# Reflow-A-Tron.net
KiCad netlist of a schematic drawn in EAGLE
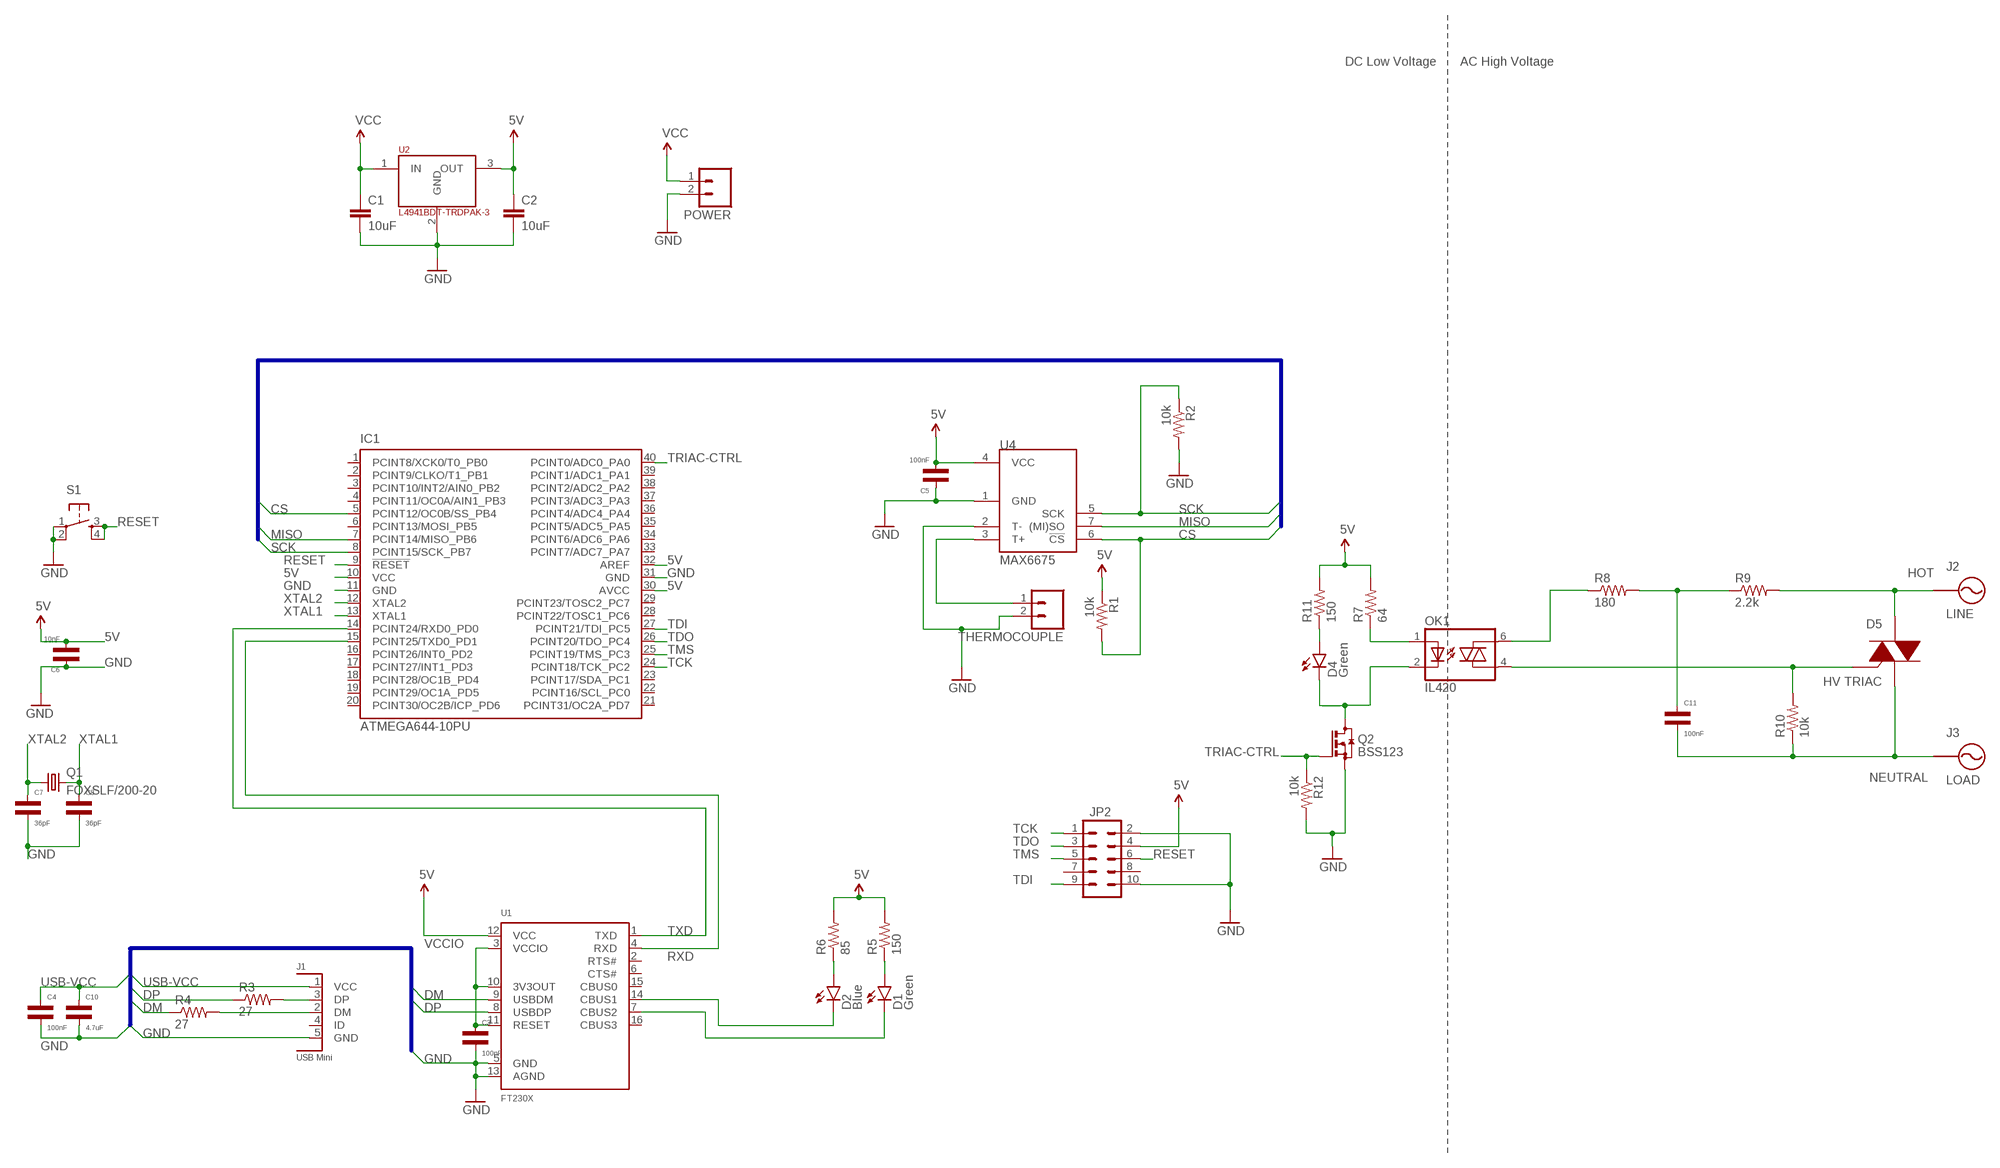
[diagram p0: schematic, sheet 1]

(export (version "E")
  (design (tool "Eeschema 10.0.6"))
  (components
    (comp (ref "C1")
      (value "10uF")
      (footprint "eagle-import:1210")
      (libsource (lib "eagle-import") (part "10UF50V20%(1210)"))
    )
    (comp (ref "C2")
      (value "10uF")
      (footprint "eagle-import:1210")
      (libsource (lib "eagle-import") (part "10UF50V20%(1210)"))
    )
    (comp (ref "C3")
      (value "100nF")
      (footprint "eagle-import:0805")
      (libsource (lib "eagle-import") (part "neilbetham_SMD-CAP-0805"))
    )
    (comp (ref "C4")
      (value "100nF")
      (footprint "eagle-import:0805")
      (libsource (lib "eagle-import") (part "neilbetham_SMD-CAP-0805"))
    )
    (comp (ref "C5")
      (value "100nF")
      (footprint "eagle-import:0805")
      (libsource (lib "eagle-import") (part "SMD-CAP-0805"))
    )
    (comp (ref "C6")
      (value "10nF")
      (footprint "eagle-import:0805")
      (libsource (lib "eagle-import") (part "SMD-CAP-0805"))
    )
    (comp (ref "C7")
      (value "36pF")
      (footprint "eagle-import:0805")
      (libsource (lib "eagle-import") (part "neilbetham_SMD-CAP-0805"))
    )
    (comp (ref "C8")
      (value "36pF")
      (footprint "eagle-import:0805")
      (libsource (lib "eagle-import") (part "neilbetham_SMD-CAP-0805"))
    )
    (comp (ref "C10")
      (value "4.7uF")
      (footprint "eagle-import:0805")
      (libsource (lib "eagle-import") (part "neilbetham_SMD-CAP-0805"))
    )
    (comp (ref "C11")
      (value "100nF")
      (footprint "eagle-import:0805")
      (libsource (lib "eagle-import") (part "neilbetham_SMD-CAP-0805"))
    )
    (comp (ref "D1")
      (value "Green")
      (footprint "eagle-import:LED-1206")
      (libsource (lib "eagle-import") (part "LED1206"))
    )
    (comp (ref "D2")
      (value "Blue")
      (footprint "eagle-import:LED-1206")
      (libsource (lib "eagle-import") (part "LED1206"))
    )
    (comp (ref "D4")
      (value "Green")
      (footprint "eagle-import:LED-1206")
      (libsource (lib "eagle-import") (part "LED1206"))
    )
    (comp (ref "D5")
      (value "HV TRIAC")
      (footprint "eagle-import:D2PAK")
      (libsource (lib "eagle-import") (part "T1250H"))
    )
    (comp (ref "IC1")
      (value "ATMEGA644-10PU")
      (footprint "eagle-import:DIL40")
      (fields (field (name "MPN") "ATMEGA644V-10PU"))
      (libsource (lib "eagle-import") (part "ATMEGA644-PU10"))
    )
    (comp (ref "J1")
      (value "USB Mini")
      (footprint "eagle-import:XM7D-0512")
      (libsource (lib "eagle-import") (part "XM7D-0512"))
    )
    (comp (ref "J2")
      (value "LINE")
      (footprint "eagle-import:8191")
      (libsource (lib "eagle-import") (part "8191"))
    )
    (comp (ref "J3")
      (value "LOAD")
      (footprint "eagle-import:8191")
      (libsource (lib "eagle-import") (part "8191"))
    )
    (comp (ref "JP2")
      (value "M05X2PTH")
      (footprint "eagle-import:AVR_ICSP")
      (libsource (lib "eagle-import") (part "M05X2PTH"))
    )
    (comp (ref "OK1")
      (value "IL420")
      (footprint "eagle-import:DIL06")
      (fields (field (name "MF") "VISHAY/TELEFUNKEN"))
      (libsource (lib "eagle-import") (part "IL420"))
    )
    (comp (ref "POWER")
      (value "M025MM")
      (footprint "eagle-import:SCREWTERMINAL-5MM-2")
      (libsource (lib "eagle-import") (part "M025MM"))
    )
    (comp (ref "Q1")
      (value "FOXSLF/200-20")
      (footprint "eagle-import:HC49_S")
      (libsource (lib "eagle-import") (part "CRYSTALHC49S"))
    )
    (comp (ref "Q2")
      (value "BSS123")
      (footprint "eagle-import:SOT23")
      (libsource (lib "eagle-import") (part "BSS123"))
    )
    (comp (ref "R1")
      (value "10k")
      (footprint "eagle-import:R0805")
      (libsource (lib "eagle-import") (part "R-US_R0805"))
    )
    (comp (ref "R2")
      (value "10k")
      (footprint "eagle-import:R0805")
      (libsource (lib "eagle-import") (part "R-US_R0805"))
    )
    (comp (ref "R3")
      (value "27")
      (footprint "eagle-import:M0805")
      (libsource (lib "eagle-import") (part "R-US_M0805"))
    )
    (comp (ref "R4")
      (value "27")
      (footprint "eagle-import:M0805")
      (libsource (lib "eagle-import") (part "R-US_M0805"))
    )
    (comp (ref "R5")
      (value "150")
      (footprint "eagle-import:R0805")
      (libsource (lib "eagle-import") (part "R-US_R0805"))
    )
    (comp (ref "R6")
      (value "85")
      (footprint "eagle-import:R0805")
      (libsource (lib "eagle-import") (part "R-US_R0805"))
    )
    (comp (ref "R7")
      (value "64")
      (footprint "eagle-import:R0805")
      (libsource (lib "eagle-import") (part "R-US_R0805"))
    )
    (comp (ref "R8")
      (value "180")
      (footprint "eagle-import:R0805")
      (libsource (lib "eagle-import") (part "R-US_R0805"))
    )
    (comp (ref "R9")
      (value "2.2k")
      (footprint "eagle-import:R0805")
      (libsource (lib "eagle-import") (part "R-US_R0805"))
    )
    (comp (ref "R10")
      (value "10k")
      (footprint "eagle-import:R0805")
      (libsource (lib "eagle-import") (part "R-US_R0805"))
    )
    (comp (ref "R11")
      (value "150")
      (footprint "eagle-import:R0805")
      (libsource (lib "eagle-import") (part "R-US_R0805"))
    )
    (comp (ref "R12")
      (value "10k")
      (footprint "eagle-import:R0805")
      (libsource (lib "eagle-import") (part "R-US_R0805"))
    )
    (comp (ref "S1")
      (value "TAC_SWITCHPTH")
      (footprint "eagle-import:TACTILE-PTH")
      (libsource (lib "eagle-import") (part "TAC_SWITCHPTH"))
    )
    (comp (ref "THERMOCOUPLE")
      (value "M023.5MM")
      (footprint "eagle-import:SCREWTERMINAL-3.5MM-2")
      (libsource (lib "eagle-import") (part "M023.5MM"))
    )
    (comp (ref "U1")
      (value "FT230X")
      (footprint "eagle-import:SSOP-16")
      (libsource (lib "eagle-import") (part "FT230X"))
    )
    (comp (ref "U2")
      (value "L4941BDT-TRDPAK-3")
      (footprint "eagle-import:DPAK")
      (libsource (lib "eagle-import") (part "L4941BDT-TRDPAK-3"))
    )
    (comp (ref "U4")
      (value "MAX6675")
      (footprint "eagle-import:SOIC8")
      (libsource (lib "eagle-import") (part "MAX6675"))
    )
  )
  (nets
    (net (code "1") (name "/CS") (class "Default")
      (node (ref "IC1") (pin "5") (pinfunction "PCINT12/OC0B/SS_PB4_5") (pintype "bidirectional"))
      (node (ref "R1") (pin "2") (pinfunction "2_2") (pintype "passive"))
      (node (ref "U4") (pin "6") (pinfunction "~{CS}_6") (pintype "bidirectional"))
    )
    (net (code "2") (name "/DM") (class "Default")
      (node (ref "R4") (pin "1") (pinfunction "1_1") (pintype "passive"))
      (node (ref "U1") (pin "9") (pinfunction "USBDM_9") (pintype "bidirectional"))
    )
    (net (code "3") (name "/DP") (class "Default")
      (node (ref "R3") (pin "1") (pinfunction "1_1") (pintype "passive"))
      (node (ref "U1") (pin "8") (pinfunction "USBDP_8") (pintype "bidirectional"))
    )
    (net (code "4") (name "/HOT") (class "Default")
      (node (ref "D5") (pin "4") (pinfunction "A2_4") (pintype "bidirectional"))
      (node (ref "J2") (pin "1") (pinfunction "1_1") (pintype "bidirectional"))
      (node (ref "J2") (pin "2") (pinfunction "1_2") (pintype "bidirectional"))
      (node (ref "J2") (pin "3") (pinfunction "1_3") (pintype "bidirectional"))
      (node (ref "J2") (pin "4") (pinfunction "1_4") (pintype "bidirectional"))
      (node (ref "R9") (pin "2") (pinfunction "2_2") (pintype "passive"))
    )
    (net (code "5") (name "/MISO") (class "Default")
      (node (ref "IC1") (pin "7") (pinfunction "PCINT14/MISO_PB6_7") (pintype "bidirectional"))
      (node (ref "U4") (pin "7") (pinfunction "(MI)SO_7") (pintype "bidirectional"))
    )
    (net (code "6") (name "/NEUTRAL") (class "Default")
      (node (ref "C11") (pin "1") (pinfunction "1_1") (pintype "bidirectional"))
      (node (ref "D5") (pin "1") (pinfunction "A1_1") (pintype "bidirectional"))
      (node (ref "J3") (pin "1") (pinfunction "1_1") (pintype "bidirectional"))
      (node (ref "J3") (pin "2") (pinfunction "1_2") (pintype "bidirectional"))
      (node (ref "J3") (pin "3") (pinfunction "1_3") (pintype "bidirectional"))
      (node (ref "J3") (pin "4") (pinfunction "1_4") (pintype "bidirectional"))
      (node (ref "R10") (pin "1") (pinfunction "1_1") (pintype "passive"))
    )
    (net (code "7") (name "/RESET") (class "Default")
      (node (ref "IC1") (pin "9") (pinfunction "~{RESET}_9") (pintype "input"))
      (node (ref "JP2") (pin "6") (pinfunction "6_6") (pintype "passive"))
      (node (ref "S1") (pin "3") (pinfunction "3_3") (pintype "passive"))
      (node (ref "S1") (pin "4") (pinfunction "4_4") (pintype "passive"))
    )
    (net (code "8") (name "/RXD") (class "Default")
      (node (ref "IC1") (pin "15") (pinfunction "PCINT25/TXD0_PD1_15") (pintype "bidirectional"))
      (node (ref "U1") (pin "4") (pinfunction "RXD_4") (pintype "bidirectional"))
    )
    (net (code "9") (name "/SCK") (class "Default")
      (node (ref "IC1") (pin "8") (pinfunction "PCINT15/SCK_PB7_8") (pintype "bidirectional"))
      (node (ref "R2") (pin "1") (pinfunction "1_1") (pintype "passive"))
      (node (ref "U4") (pin "5") (pinfunction "SCK_5") (pintype "bidirectional"))
    )
    (net (code "10") (name "/TCK") (class "Default")
      (node (ref "IC1") (pin "24") (pinfunction "PCINT18/TCK_PC2_24") (pintype "bidirectional"))
      (node (ref "JP2") (pin "1") (pinfunction "1_1") (pintype "passive"))
    )
    (net (code "11") (name "/TDI") (class "Default")
      (node (ref "IC1") (pin "27") (pinfunction "PCINT21/TDI_PC5_27") (pintype "bidirectional"))
      (node (ref "JP2") (pin "9") (pinfunction "9_9") (pintype "passive"))
    )
    (net (code "12") (name "/TDO") (class "Default")
      (node (ref "IC1") (pin "26") (pinfunction "PCINT20/TDO_PC4_26") (pintype "bidirectional"))
      (node (ref "JP2") (pin "3") (pinfunction "3_3") (pintype "passive"))
    )
    (net (code "13") (name "/TMS") (class "Default")
      (node (ref "IC1") (pin "25") (pinfunction "PCINT19/TMS_PC3_25") (pintype "bidirectional"))
      (node (ref "JP2") (pin "5") (pinfunction "5_5") (pintype "passive"))
    )
    (net (code "14") (name "/TRIAC-CTRL") (class "Default")
      (node (ref "IC1") (pin "40") (pinfunction "PCINT0/ADC0_PA0_40") (pintype "bidirectional"))
      (node (ref "Q2") (pin "1") (pinfunction "G_1") (pintype "passive"))
      (node (ref "R12") (pin "1") (pinfunction "1_1") (pintype "passive"))
    )
    (net (code "15") (name "/TXD") (class "Default")
      (node (ref "IC1") (pin "14") (pinfunction "PCINT24/RXD0_PD0_14") (pintype "bidirectional"))
      (node (ref "U1") (pin "1") (pinfunction "TXD_1") (pintype "bidirectional"))
    )
    (net (code "16") (name "/USB-VCC") (class "Default")
      (node (ref "C10") (pin "2") (pinfunction "2_2") (pintype "bidirectional"))
      (node (ref "C4") (pin "2") (pinfunction "2_2") (pintype "bidirectional"))
      (node (ref "J1") (pin "1") (pinfunction "VCC_1") (pintype "bidirectional"))
    )
    (net (code "17") (name "/VCCIO") (class "Default")
      (node (ref "C3") (pin "2") (pinfunction "2_2") (pintype "bidirectional"))
      (node (ref "U1") (pin "10") (pinfunction "3V3OUT_10") (pintype "bidirectional"))
      (node (ref "U1") (pin "11") (pinfunction "RESET_11") (pintype "bidirectional"))
      (node (ref "U1") (pin "3") (pinfunction "VCCIO_3") (pintype "bidirectional"))
    )
    (net (code "18") (name "/XTAL1") (class "Default")
      (node (ref "C8") (pin "2") (pinfunction "2_2") (pintype "bidirectional"))
      (node (ref "IC1") (pin "13") (pinfunction "XTAL1_13") (pintype "input"))
      (node (ref "Q1") (pin "2") (pinfunction "2_2") (pintype "passive"))
    )
    (net (code "19") (name "/XTAL2") (class "Default")
      (node (ref "C7") (pin "2") (pinfunction "2_2") (pintype "bidirectional"))
      (node (ref "IC1") (pin "12") (pinfunction "XTAL2_12") (pintype "output"))
      (node (ref "Q1") (pin "1") (pinfunction "1_1") (pintype "passive"))
    )
    (net (code "20") (name "5V") (class "Default")
      (node (ref "C2") (pin "1") (pinfunction "1_1") (pintype "passive"))
      (node (ref "C5") (pin "1") (pinfunction "1_1") (pintype "bidirectional"))
      (node (ref "C6") (pin "1") (pinfunction "1_1") (pintype "bidirectional"))
      (node (ref "IC1") (pin "10") (pinfunction "VCC_10") (pintype "power_in"))
      (node (ref "IC1") (pin "30") (pinfunction "AVCC_30") (pintype "power_in"))
      (node (ref "IC1") (pin "32") (pinfunction "AREF_32") (pintype "passive"))
      (node (ref "JP2") (pin "4") (pinfunction "4_4") (pintype "passive"))
      (node (ref "R1") (pin "1") (pinfunction "1_1") (pintype "passive"))
      (node (ref "R11") (pin "2") (pinfunction "2_2") (pintype "passive"))
      (node (ref "R5") (pin "2") (pinfunction "2_2") (pintype "passive"))
      (node (ref "R6") (pin "2") (pinfunction "2_2") (pintype "passive"))
      (node (ref "R7") (pin "2") (pinfunction "2_2") (pintype "passive"))
      (node (ref "U1") (pin "12") (pinfunction "VCC_12") (pintype "bidirectional"))
      (node (ref "U2") (pin "3") (pinfunction "OUT_3") (pintype "bidirectional"))
      (node (ref "U4") (pin "4") (pinfunction "VCC_4") (pintype "bidirectional"))
    )
    (net (code "21") (name "GND") (class "Default")
      (node (ref "C1") (pin "2") (pinfunction "2_2") (pintype "passive"))
      (node (ref "C10") (pin "1") (pinfunction "1_1") (pintype "bidirectional"))
      (node (ref "C2") (pin "2") (pinfunction "2_2") (pintype "passive"))
      (node (ref "C3") (pin "1") (pinfunction "1_1") (pintype "bidirectional"))
      (node (ref "C4") (pin "1") (pinfunction "1_1") (pintype "bidirectional"))
      (node (ref "C5") (pin "2") (pinfunction "2_2") (pintype "bidirectional"))
      (node (ref "C6") (pin "2") (pinfunction "2_2") (pintype "bidirectional"))
      (node (ref "C7") (pin "1") (pinfunction "1_1") (pintype "bidirectional"))
      (node (ref "C8") (pin "1") (pinfunction "1_1") (pintype "bidirectional"))
      (node (ref "IC1") (pin "11") (pinfunction "GND_11") (pintype "power_in"))
      (node (ref "IC1") (pin "31") (pinfunction "GND_31") (pintype "power_in"))
      (node (ref "J1") (pin "5") (pinfunction "GND_5") (pintype "bidirectional"))
      (node (ref "JP2") (pin "10") (pinfunction "10_10") (pintype "passive"))
      (node (ref "JP2") (pin "2") (pinfunction "2_2") (pintype "passive"))
      (node (ref "POWER") (pin "2") (pinfunction "2_2") (pintype "passive"))
      (node (ref "Q2") (pin "2") (pinfunction "S_2") (pintype "passive"))
      (node (ref "R12") (pin "2") (pinfunction "2_2") (pintype "passive"))
      (node (ref "R2") (pin "2") (pinfunction "2_2") (pintype "passive"))
      (node (ref "S1") (pin "1") (pinfunction "1_1") (pintype "passive"))
      (node (ref "S1") (pin "2") (pinfunction "2_2") (pintype "passive"))
      (node (ref "THERMOCOUPLE") (pin "2") (pinfunction "2_2") (pintype "passive"))
      (node (ref "U1") (pin "13") (pinfunction "AGND_13") (pintype "bidirectional"))
      (node (ref "U1") (pin "5") (pinfunction "GND_5") (pintype "bidirectional"))
      (node (ref "U2") (pin "2") (pinfunction "GND_2") (pintype "bidirectional"))
      (node (ref "U4") (pin "1") (pinfunction "GND_1") (pintype "bidirectional"))
      (node (ref "U4") (pin "2") (pinfunction "T-_2") (pintype "bidirectional"))
    )
    (net (code "22") (name "Net-(C11-Pad2)") (class "Default")
      (node (ref "C11") (pin "2") (pinfunction "2_2") (pintype "bidirectional"))
      (node (ref "R8") (pin "2") (pinfunction "2_2") (pintype "passive"))
      (node (ref "R9") (pin "1") (pinfunction "1_1") (pintype "passive"))
    )
    (net (code "23") (name "Net-(D1-PadA)") (class "Default")
      (node (ref "D1") (pin "A") (pinfunction "A_A") (pintype "passive"))
      (node (ref "R5") (pin "1") (pinfunction "1_1") (pintype "passive"))
    )
    (net (code "24") (name "Net-(D2-PadA)") (class "Default")
      (node (ref "D2") (pin "A") (pinfunction "A_A") (pintype "passive"))
      (node (ref "R6") (pin "1") (pinfunction "1_1") (pintype "passive"))
    )
    (net (code "25") (name "Net-(D4-PadA)") (class "Default")
      (node (ref "D4") (pin "A") (pinfunction "A_A") (pintype "passive"))
      (node (ref "R11") (pin "1") (pinfunction "1_1") (pintype "passive"))
    )
    (net (code "26") (name "Net-(D5-G)") (class "Default")
      (node (ref "D5") (pin "3") (pinfunction "G_3") (pintype "bidirectional"))
      (node (ref "OK1") (pin "4") (pinfunction "A1_4") (pintype "passive"))
      (node (ref "R10") (pin "2") (pinfunction "2_2") (pintype "passive"))
    )
    (net (code "27") (name "Net-(J1-DM)") (class "Default")
      (node (ref "J1") (pin "2") (pinfunction "DM_2") (pintype "bidirectional"))
      (node (ref "R4") (pin "2") (pinfunction "2_2") (pintype "passive"))
    )
    (net (code "28") (name "Net-(J1-DP)") (class "Default")
      (node (ref "J1") (pin "3") (pinfunction "DP_3") (pintype "bidirectional"))
      (node (ref "R3") (pin "2") (pinfunction "2_2") (pintype "passive"))
    )
    (net (code "29") (name "Net-(OK1-A)") (class "Default")
      (node (ref "OK1") (pin "1") (pinfunction "A_1") (pintype "passive"))
      (node (ref "R7") (pin "1") (pinfunction "1_1") (pintype "passive"))
    )
    (net (code "30") (name "Net-(OK1-A2)") (class "Default")
      (node (ref "OK1") (pin "6") (pinfunction "A2_6") (pintype "passive"))
      (node (ref "R8") (pin "1") (pinfunction "1_1") (pintype "passive"))
    )
    (net (code "31") (name "Net-(OK1-C)") (class "Default")
      (node (ref "D4") (pin "C") (pinfunction "C_C") (pintype "passive"))
      (node (ref "OK1") (pin "2") (pinfunction "C_2") (pintype "passive"))
      (node (ref "Q2") (pin "3") (pinfunction "D_3") (pintype "passive"))
    )
    (net (code "32") (name "Net-(U1-CBUS1)") (class "Default")
      (node (ref "D2") (pin "C") (pinfunction "C_C") (pintype "passive"))
      (node (ref "U1") (pin "14") (pinfunction "CBUS1_14") (pintype "bidirectional"))
    )
    (net (code "33") (name "Net-(U1-CBUS2)") (class "Default")
      (node (ref "D1") (pin "C") (pinfunction "C_C") (pintype "passive"))
      (node (ref "U1") (pin "7") (pinfunction "CBUS2_7") (pintype "bidirectional"))
    )
    (net (code "34") (name "Net-(U4-T+)") (class "Default")
      (node (ref "THERMOCOUPLE") (pin "1") (pinfunction "1_1") (pintype "passive"))
      (node (ref "U4") (pin "3") (pinfunction "T+_3") (pintype "bidirectional"))
    )
    (net (code "35") (name "VCC") (class "Default")
      (node (ref "C1") (pin "1") (pinfunction "1_1") (pintype "passive"))
      (node (ref "POWER") (pin "1") (pinfunction "1_1") (pintype "passive"))
      (node (ref "U2") (pin "1") (pinfunction "IN_1") (pintype "bidirectional"))
    )
    (net (code "36") (name "unconnected-(IC1-PCINT1{slash}ADC1_PA1-Pad39)") (class "Default")
      (node (ref "IC1") (pin "39") (pinfunction "PCINT1/ADC1_PA1_39") (pintype "bidirectional"))
    )
    (net (code "37") (name "unconnected-(IC1-PCINT2{slash}ADC2_PA2-Pad38)") (class "Default")
      (node (ref "IC1") (pin "38") (pinfunction "PCINT2/ADC2_PA2_38") (pintype "bidirectional"))
    )
    (net (code "38") (name "unconnected-(IC1-PCINT3{slash}ADC3_PA3-Pad37)") (class "Default")
      (node (ref "IC1") (pin "37") (pinfunction "PCINT3/ADC3_PA3_37") (pintype "bidirectional"))
    )
    (net (code "39") (name "unconnected-(IC1-PCINT4{slash}ADC4_PA4-Pad36)") (class "Default")
      (node (ref "IC1") (pin "36") (pinfunction "PCINT4/ADC4_PA4_36") (pintype "bidirectional"))
    )
    (net (code "40") (name "unconnected-(IC1-PCINT5{slash}ADC5_PA5-Pad35)") (class "Default")
      (node (ref "IC1") (pin "35") (pinfunction "PCINT5/ADC5_PA5_35") (pintype "bidirectional"))
    )
    (net (code "41") (name "unconnected-(IC1-PCINT6{slash}ADC6_PA6-Pad34)") (class "Default")
      (node (ref "IC1") (pin "34") (pinfunction "PCINT6/ADC6_PA6_34") (pintype "bidirectional"))
    )
    (net (code "42") (name "unconnected-(IC1-PCINT7{slash}ADC7_PA7-Pad33)") (class "Default")
      (node (ref "IC1") (pin "33") (pinfunction "PCINT7/ADC7_PA7_33") (pintype "bidirectional"))
    )
    (net (code "43") (name "unconnected-(IC1-PCINT8{slash}XCK0{slash}T0_PB0-Pad1)") (class "Default")
      (node (ref "IC1") (pin "1") (pinfunction "PCINT8/XCK0/T0_PB0_1") (pintype "bidirectional"))
    )
    (net (code "44") (name "unconnected-(IC1-PCINT9{slash}CLKO{slash}T1_PB1-Pad2)") (class "Default")
      (node (ref "IC1") (pin "2") (pinfunction "PCINT9/CLKO/T1_PB1_2") (pintype "bidirectional"))
    )
    (net (code "45") (name "unconnected-(IC1-PCINT10{slash}INT2{slash}AIN0_PB2-Pad3)") (class "Default")
      (node (ref "IC1") (pin "3") (pinfunction "PCINT10/INT2/AIN0_PB2_3") (pintype "bidirectional"))
    )
    (net (code "46") (name "unconnected-(IC1-PCINT11{slash}OC0A{slash}AIN1_PB3-Pad4)") (class "Default")
      (node (ref "IC1") (pin "4") (pinfunction "PCINT11/OC0A/AIN1_PB3_4") (pintype "bidirectional"))
    )
    (net (code "47") (name "unconnected-(IC1-PCINT13{slash}MOSI_PB5-Pad6)") (class "Default")
      (node (ref "IC1") (pin "6") (pinfunction "PCINT13/MOSI_PB5_6") (pintype "bidirectional"))
    )
    (net (code "48") (name "unconnected-(IC1-PCINT16{slash}SCL_PC0-Pad22)") (class "Default")
      (node (ref "IC1") (pin "22") (pinfunction "PCINT16/SCL_PC0_22") (pintype "bidirectional"))
    )
    (net (code "49") (name "unconnected-(IC1-PCINT17{slash}SDA_PC1-Pad23)") (class "Default")
      (node (ref "IC1") (pin "23") (pinfunction "PCINT17/SDA_PC1_23") (pintype "bidirectional"))
    )
    (net (code "50") (name "unconnected-(IC1-PCINT22{slash}TOSC1_PC6-Pad28)") (class "Default")
      (node (ref "IC1") (pin "28") (pinfunction "PCINT22/TOSC1_PC6_28") (pintype "bidirectional"))
    )
    (net (code "51") (name "unconnected-(IC1-PCINT23{slash}TOSC2_PC7-Pad29)") (class "Default")
      (node (ref "IC1") (pin "29") (pinfunction "PCINT23/TOSC2_PC7_29") (pintype "bidirectional"))
    )
    (net (code "52") (name "unconnected-(IC1-PCINT26{slash}INT0_PD2-Pad16)") (class "Default")
      (node (ref "IC1") (pin "16") (pinfunction "PCINT26/INT0_PD2_16") (pintype "bidirectional"))
    )
    (net (code "53") (name "unconnected-(IC1-PCINT27{slash}INT1_PD3-Pad17)") (class "Default")
      (node (ref "IC1") (pin "17") (pinfunction "PCINT27/INT1_PD3_17") (pintype "bidirectional"))
    )
    (net (code "54") (name "unconnected-(IC1-PCINT28{slash}OC1B_PD4-Pad18)") (class "Default")
      (node (ref "IC1") (pin "18") (pinfunction "PCINT28/OC1B_PD4_18") (pintype "bidirectional"))
    )
    (net (code "55") (name "unconnected-(IC1-PCINT29{slash}OC1A_PD5-Pad19)") (class "Default")
      (node (ref "IC1") (pin "19") (pinfunction "PCINT29/OC1A_PD5_19") (pintype "bidirectional"))
    )
    (net (code "56") (name "unconnected-(IC1-PCINT30{slash}OC2B{slash}ICP_PD6-Pad20)") (class "Default")
      (node (ref "IC1") (pin "20") (pinfunction "PCINT30/OC2B/ICP_PD6_20") (pintype "bidirectional"))
    )
    (net (code "57") (name "unconnected-(IC1-PCINT31{slash}OC2A_PD7-Pad21)") (class "Default")
      (node (ref "IC1") (pin "21") (pinfunction "PCINT31/OC2A_PD7_21") (pintype "bidirectional"))
    )
    (net (code "58") (name "unconnected-(J1-ID-Pad4)") (class "Default")
      (node (ref "J1") (pin "4") (pinfunction "ID_4") (pintype "bidirectional"))
    )
    (net (code "59") (name "unconnected-(JP2-Pad7)") (class "Default")
      (node (ref "JP2") (pin "7") (pinfunction "7_7") (pintype "passive"))
    )
    (net (code "60") (name "unconnected-(JP2-Pad8)") (class "Default")
      (node (ref "JP2") (pin "8") (pinfunction "8_8") (pintype "passive"))
    )
    (net (code "61") (name "unconnected-(U1-CBUS0-Pad15)") (class "Default")
      (node (ref "U1") (pin "15") (pinfunction "CBUS0_15") (pintype "bidirectional"))
    )
    (net (code "62") (name "unconnected-(U1-CBUS3-Pad16)") (class "Default")
      (node (ref "U1") (pin "16") (pinfunction "CBUS3_16") (pintype "bidirectional"))
    )
    (net (code "63") (name "unconnected-(U1-CTS#-Pad6)") (class "Default")
      (node (ref "U1") (pin "6") (pinfunction "CTS#_6") (pintype "bidirectional"))
    )
    (net (code "64") (name "unconnected-(U1-RTS#-Pad2)") (class "Default")
      (node (ref "U1") (pin "2") (pinfunction "RTS#_2") (pintype "bidirectional"))
    )
  )
)
